# Schema_Proiect_v121.net
KiCad netlist of a schematic drawn in EAGLE
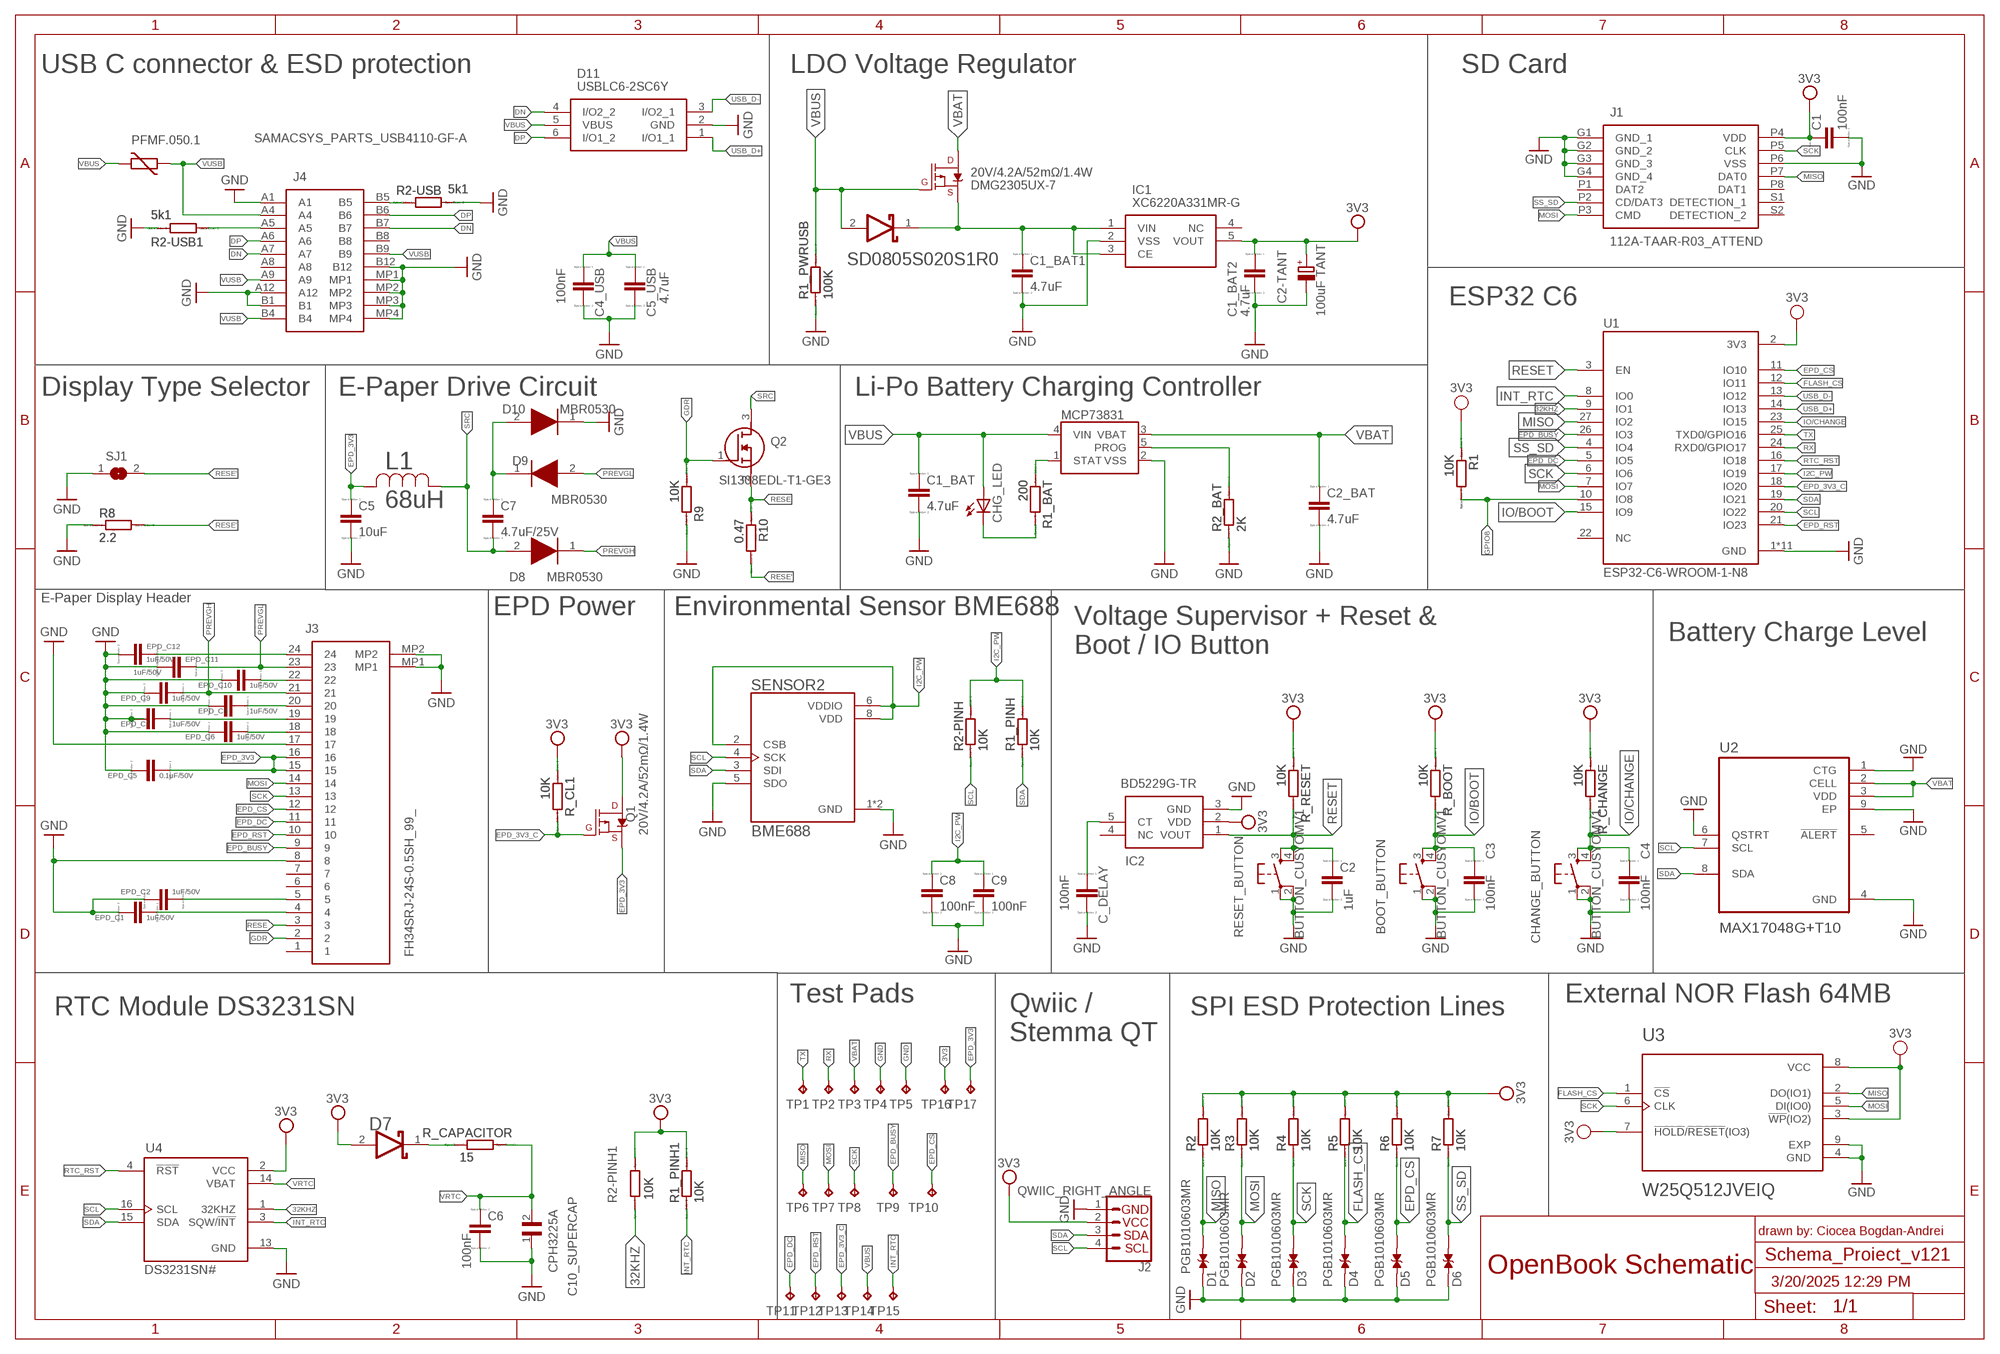
[diagram p0: schematic, sheet 1]

(export (version "E")
  (design (tool "Eeschema 10.0.6"))
  (components
    (comp (ref "BOOT_BUTTON")
      (value "BUTTON_CUSYOMV1")
      (footprint "eagle-import:MYBUTTON")
      (libsource (lib "eagle-import") (part "BUTTON_CUSYOMV1"))
    )
    (comp (ref "C1")
      (value "100nF")
      (footprint "eagle-import:EAGLE-LTSPICE_C0402")
      (libsource (lib "eagle-import") (part "EAGLE-LTSPICE_CC0402"))
    )
    (comp (ref "C1_BAT")
      (value "4.7uF")
      (footprint "eagle-import:EAGLE-LTSPICE_C0402")
      (libsource (lib "eagle-import") (part "EAGLE-LTSPICE_CC0402"))
    )
    (comp (ref "C1_BAT1")
      (value "4.7uF")
      (footprint "eagle-import:EAGLE-LTSPICE_C0402")
      (libsource (lib "eagle-import") (part "EAGLE-LTSPICE_CC0402"))
    )
    (comp (ref "C1_BAT2")
      (value "4.7uF")
      (footprint "eagle-import:EAGLE-LTSPICE_C0402")
      (libsource (lib "eagle-import") (part "EAGLE-LTSPICE_CC0402"))
    )
    (comp (ref "C2")
      (value "1uF")
      (footprint "eagle-import:EAGLE-LTSPICE_C0402")
      (libsource (lib "eagle-import") (part "EAGLE-LTSPICE_CC0402"))
    )
    (comp (ref "C2-TANT")
      (value "100uF TANT")
      (footprint "eagle-import:RCL_CT3528")
      (libsource (lib "eagle-import") (part "RCL_CPOL-EUCT3528"))
    )
    (comp (ref "C2_BAT")
      (value "4.7uF")
      (footprint "eagle-import:EAGLE-LTSPICE_C0402")
      (libsource (lib "eagle-import") (part "EAGLE-LTSPICE_CC0402"))
    )
    (comp (ref "C3")
      (value "100nF")
      (footprint "eagle-import:EAGLE-LTSPICE_C0402")
      (libsource (lib "eagle-import") (part "EAGLE-LTSPICE_CC0402"))
    )
    (comp (ref "C4")
      (value "100nF")
      (footprint "eagle-import:EAGLE-LTSPICE_C0402")
      (libsource (lib "eagle-import") (part "EAGLE-LTSPICE_CC0402"))
    )
    (comp (ref "C4_USB")
      (value "100nF")
      (footprint "eagle-import:EAGLE-LTSPICE_C0402")
      (libsource (lib "eagle-import") (part "EAGLE-LTSPICE_CC0402"))
    )
    (comp (ref "C5")
      (value "10uF")
      (footprint "eagle-import:EAGLE-LTSPICE_C0402")
      (libsource (lib "eagle-import") (part "EAGLE-LTSPICE_CC0402"))
    )
    (comp (ref "C5_USB")
      (value "4.7uF")
      (footprint "eagle-import:EAGLE-LTSPICE_C0402")
      (libsource (lib "eagle-import") (part "EAGLE-LTSPICE_CC0402"))
    )
    (comp (ref "C6")
      (value "100nF")
      (footprint "eagle-import:EAGLE-LTSPICE_C0402")
      (libsource (lib "eagle-import") (part "EAGLE-LTSPICE_CC0402"))
    )
    (comp (ref "C7")
      (value "4.7uF/25V")
      (footprint "eagle-import:EAGLE-LTSPICE_C0402")
      (libsource (lib "eagle-import") (part "EAGLE-LTSPICE_CC0402"))
    )
    (comp (ref "C8")
      (value "100nF")
      (footprint "eagle-import:EAGLE-LTSPICE_C0402")
      (libsource (lib "eagle-import") (part "EAGLE-LTSPICE_CC0402"))
    )
    (comp (ref "C9")
      (value "100nF")
      (footprint "eagle-import:EAGLE-LTSPICE_C0402")
      (libsource (lib "eagle-import") (part "EAGLE-LTSPICE_CC0402"))
    )
    (comp (ref "C10_SUPERCAP")
      (value "CPH3225A")
      (footprint "eagle-import:CAPCP3225X100N")
      (fields (field (name "MF") "Seiko Instruments"))
      (libsource (lib "eagle-import") (part "CPH3225A"))
    )
    (comp (ref "CHANGE_BUTTON")
      (value "BUTTON_CUSYOMV1")
      (footprint "eagle-import:MYBUTTON")
      (libsource (lib "eagle-import") (part "BUTTON_CUSYOMV1"))
    )
    (comp (ref "CHG_LED")
      (value "ADAFRUIT_LEDCHIP-LED0603")
      (footprint "eagle-import:ADAFRUIT_CHIP-LED0603")
      (libsource (lib "eagle-import") (part "ADAFRUIT_LEDCHIP-LED0603"))
    )
    (comp (ref "C_DELAY")
      (value "100nF")
      (footprint "eagle-import:EAGLE-LTSPICE_C0402")
      (libsource (lib "eagle-import") (part "EAGLE-LTSPICE_CC0402"))
    )
    (comp (ref "D1")
      (value "PGB1010603MR")
      (footprint "eagle-import:DIOC1608X36N")
      (fields (field (name "MF") "Littelfuse Inc."))
      (libsource (lib "eagle-import") (part "PGB1010603MR"))
    )
    (comp (ref "D2")
      (value "PGB1010603MR")
      (footprint "eagle-import:DIOC1608X36N")
      (fields (field (name "MF") "Littelfuse Inc."))
      (libsource (lib "eagle-import") (part "PGB1010603MR"))
    )
    (comp (ref "D3")
      (value "PGB1010603MR")
      (footprint "eagle-import:DIOC1608X36N")
      (fields (field (name "MF") "Littelfuse Inc."))
      (libsource (lib "eagle-import") (part "PGB1010603MR"))
    )
    (comp (ref "D4")
      (value "PGB1010603MR")
      (footprint "eagle-import:DIOC1608X36N")
      (fields (field (name "MF") "Littelfuse Inc."))
      (libsource (lib "eagle-import") (part "PGB1010603MR"))
    )
    (comp (ref "D5")
      (value "PGB1010603MR")
      (footprint "eagle-import:DIOC1608X36N")
      (fields (field (name "MF") "Littelfuse Inc."))
      (libsource (lib "eagle-import") (part "PGB1010603MR"))
    )
    (comp (ref "D6")
      (value "PGB1010603MR")
      (footprint "eagle-import:DIOC1608X36N")
      (fields (field (name "MF") "Littelfuse Inc."))
      (libsource (lib "eagle-import") (part "PGB1010603MR"))
    )
    (comp (ref "D7")
      (value "SD0805S020S1R0")
      (footprint "eagle-import:ESP32_WROVER_AVX---SD0805S020S1R0_AVX_SD0805S020S1R0_0")
      (fields
        (field (name "DIGIKEY_PART_NUMBER") "478-7800-1-ND")
        (field (name "MF") "AVX")
        (field (name "MOUSER_PART_NUMBER") "581-SD0805S020S1R0")
      )
      (libsource (lib "eagle-import") (part "ESP32_WROVER_AVX---SD0805S020S1R0_AVX_SD0805S020S1R0_0_0AVX_SD0805S020S1R0_0_0"))
    )
    (comp (ref "D8")
      (value "MBR0530")
      (footprint "eagle-import:SOD3716X135N")
      (fields (field (name "MF") "ON Semiconductor"))
      (libsource (lib "eagle-import") (part "MBR0530"))
    )
    (comp (ref "D9")
      (value "MBR0530")
      (footprint "eagle-import:SOD3716X135N")
      (fields (field (name "MF") "ON Semiconductor"))
      (libsource (lib "eagle-import") (part "MBR0530"))
    )
    (comp (ref "D10")
      (value "MBR0530")
      (footprint "eagle-import:SOD3716X135N")
      (fields (field (name "MF") "ON Semiconductor"))
      (libsource (lib "eagle-import") (part "MBR0530"))
    )
    (comp (ref "D11")
      (value "USBLC6-2SC6Y")
      (footprint "eagle-import:SOT95P280X145-6N")
      (fields (field (name "MF") "STMicroelectronics"))
      (libsource (lib "eagle-import") (part "USBLC6-2SC6Y"))
    )
    (comp (ref "DMG2305UX-7")
      (value "20V/4.2A/52mΩ/1.4W")
      (footprint "eagle-import:ESP32_WROVER_SPARKFUN-DISCRETESEMI_SOT23-3")
      (libsource (lib "eagle-import") (part "ESP32_WROVER_SPARKFUN-DISCRETESEMI_MOSFET_PCH-DMG2305UX-7"))
    )
    (comp (ref "EPD_C1")
      (value "1uF/50V")
      (footprint "eagle-import:EAGLE-LTSPICE_C0402")
      (libsource (lib "eagle-import") (part "EAGLE-LTSPICE_CC0402"))
    )
    (comp (ref "EPD_C2")
      (value "1uF/50V")
      (footprint "eagle-import:EAGLE-LTSPICE_C0402")
      (libsource (lib "eagle-import") (part "EAGLE-LTSPICE_CC0402"))
    )
    (comp (ref "EPD_C5")
      (value "0.1uF/50V")
      (footprint "eagle-import:EAGLE-LTSPICE_C0402")
      (libsource (lib "eagle-import") (part "EAGLE-LTSPICE_CC0402"))
    )
    (comp (ref "EPD_C6")
      (value "1uF/50V")
      (footprint "eagle-import:EAGLE-LTSPICE_C0402")
      (libsource (lib "eagle-import") (part "EAGLE-LTSPICE_CC0402"))
    )
    (comp (ref "EPD_C7")
      (value "1uF/50V")
      (footprint "eagle-import:EAGLE-LTSPICE_C0402")
      (libsource (lib "eagle-import") (part "EAGLE-LTSPICE_CC0402"))
    )
    (comp (ref "EPD_C8")
      (value "1uF/50V")
      (footprint "eagle-import:EAGLE-LTSPICE_C0402")
      (libsource (lib "eagle-import") (part "EAGLE-LTSPICE_CC0402"))
    )
    (comp (ref "EPD_C9")
      (value "1uF/50V")
      (footprint "eagle-import:EAGLE-LTSPICE_C0402")
      (libsource (lib "eagle-import") (part "EAGLE-LTSPICE_CC0402"))
    )
    (comp (ref "EPD_C10")
      (value "1uF/50V")
      (footprint "eagle-import:EAGLE-LTSPICE_C0402")
      (libsource (lib "eagle-import") (part "EAGLE-LTSPICE_CC0402"))
    )
    (comp (ref "EPD_C11")
      (value "1uF/50V")
      (footprint "eagle-import:EAGLE-LTSPICE_C0402")
      (libsource (lib "eagle-import") (part "EAGLE-LTSPICE_CC0402"))
    )
    (comp (ref "EPD_C12")
      (value "1uF/50V")
      (footprint "eagle-import:EAGLE-LTSPICE_C0402")
      (libsource (lib "eagle-import") (part "EAGLE-LTSPICE_CC0402"))
    )
    (comp (ref "IC1")
      (value "XC6220A331MR-G")
      (footprint "eagle-import:SOT95P280X120-5N")
      (fields (field (name "MOUSER_PART_NUMBER") "865-XC6220A331MR-G"))
      (libsource (lib "eagle-import") (part "XC6220A331MR-G"))
    )
    (comp (ref "IC2")
      (value "BD5229G-TR")
      (footprint "eagle-import:SOT95P280X125-5N")
      (fields (field (name "MOUSER_PART_NUMBER") "755-BD5229G-TR"))
      (libsource (lib "eagle-import") (part "BD5229G-TR"))
    )
    (comp (ref "J1")
      (value "112A-TAAR-R03_ATTEND")
      (footprint "eagle-import:112ATAARR03ATTEND")
      (fields (field (name "MANUFACTURER_PART_NUMBER") "112A-TAAR-R03 ATTEND"))
      (libsource (lib "eagle-import") (part "112A-TAAR-R03_ATTEND"))
    )
    (comp (ref "J2")
      (value "QWIIC_RIGHT_ANGLE")
      (footprint "eagle-import:JST04_1MM_RA")
      (libsource (lib "eagle-import") (part "QWIIC_CONNECTORJS-1MM"))
    )
    (comp (ref "J3")
      (value "FH34SRJ-24S-0.5SH_99_")
      (footprint "eagle-import:FH34SRJ24S05SH99")
      (fields
        (field (name "MANUFACTURER_PART_NUMBER") "FH34SRJ-24S-0.5SH(99)")
        (field (name "MOUSER_PART_NUMBER") "798-FH34SRJ24S05SH99")
      )
      (libsource (lib "eagle-import") (part "FH34SRJ-24S-0.5SH_99_"))
    )
    (comp (ref "J4")
      (value "SAMACSYS_PARTS_USB4110-GF-A")
      (footprint "eagle-import:SAMACSYS_PARTS_USB4110GFA")
      (fields
        (field (name "MANUFACTURER_PART_NUMBER") "USB4110-GF-A")
        (field (name "MOUSER_PART_NUMBER") "640-USB4110-GF-A")
      )
      (libsource (lib "eagle-import") (part "SAMACSYS_PARTS_USB4110-GF-A"))
    )
    (comp (ref "L1")
      (value "68uH")
      (footprint "eagle-import:IND_4828-WE-TPC_WRE")
      (fields
        (field (name "MANUFACTURER_PART_NUMBER") "744043680")
        (field (name "COPYRIGHT") "Copyright (C) 2024 Ultra Librarian. All rights reserved.")
      )
      (libsource (lib "eagle-import") (part "744043680IND_4828-WE-TPC_WRE"))
    )
    (comp (ref "MCP73831")
      (value "ESP32_WROVER_SPARKFUN-IC-POWER_MCP73831")
      (footprint "eagle-import:ESP32_WROVER_SPARKFUN-IC-POWER_SOT23-5")
      (libsource (lib "eagle-import") (part "ESP32_WROVER_SPARKFUN-IC-POWER_MCP73831"))
    )
    (comp (ref "PFMF.050.1")
      (value "ESP32C6_VARISTORCN1812")
      (footprint "eagle-import:ESP32C6_VARISTOR_CT_CN1812")
      (libsource (lib "eagle-import") (part "ESP32C6_VARISTORCN1812"))
    )
    (comp (ref "Q1")
      (value "20V/4.2A/52mΩ/1.4W")
      (footprint "eagle-import:ESP32_WROVER_SPARKFUN-DISCRETESEMI_SOT23-3")
      (libsource (lib "eagle-import") (part "ESP32_WROVER_SPARKFUN-DISCRETESEMI_MOSFET_PCH-DMG2305UX-7"))
    )
    (comp (ref "Q2")
      (value "SI1308EDL-T1-GE3")
      (footprint "eagle-import:SOT65P210X110-3N")
      (fields (field (name "MF") "Vishay Siliconix"))
      (libsource (lib "eagle-import") (part "SI1308EDL-T1-GE3"))
    )
    (comp (ref "R1")
      (value "10K")
      (footprint "eagle-import:ESP32_WROVER_EAGLE-LTSPICE_R0402")
      (libsource (lib "eagle-import") (part "ESP32_WROVER_EAGLE-LTSPICE_RR0402"))
    )
    (comp (ref "R1_BAT")
      (value "200")
      (footprint "eagle-import:ESP32_WROVER_EAGLE-LTSPICE_R0402")
      (libsource (lib "eagle-import") (part "ESP32_WROVER_EAGLE-LTSPICE_RR0402"))
    )
    (comp (ref "R1_PINH")
      (value "10K")
      (footprint "eagle-import:ESP32_WROVER_EAGLE-LTSPICE_R0402")
      (libsource (lib "eagle-import") (part "ESP32_WROVER_EAGLE-LTSPICE_RR0402"))
    )
    (comp (ref "R1_PINH1")
      (value "10K")
      (footprint "eagle-import:ESP32_WROVER_EAGLE-LTSPICE_R0402")
      (libsource (lib "eagle-import") (part "ESP32_WROVER_EAGLE-LTSPICE_RR0402"))
    )
    (comp (ref "R1_PWRUSB")
      (value "100K")
      (footprint "eagle-import:ESP32_WROVER_EAGLE-LTSPICE_R0402")
      (libsource (lib "eagle-import") (part "ESP32_WROVER_EAGLE-LTSPICE_RR0402"))
    )
    (comp (ref "R2")
      (value "10K")
      (footprint "eagle-import:ESP32_WROVER_EAGLE-LTSPICE_R0402")
      (libsource (lib "eagle-import") (part "ESP32_WROVER_EAGLE-LTSPICE_RR0402"))
    )
    (comp (ref "R2-PINH")
      (value "10K")
      (footprint "eagle-import:ESP32_WROVER_EAGLE-LTSPICE_R0402")
      (libsource (lib "eagle-import") (part "ESP32_WROVER_EAGLE-LTSPICE_RR0402"))
    )
    (comp (ref "R2-PINH1")
      (value "10K")
      (footprint "eagle-import:ESP32_WROVER_EAGLE-LTSPICE_R0402")
      (libsource (lib "eagle-import") (part "ESP32_WROVER_EAGLE-LTSPICE_RR0402"))
    )
    (comp (ref "R2-USB")
      (value "5k1")
      (footprint "eagle-import:ESP32_WROVER_EAGLE-LTSPICE_R0402")
      (libsource (lib "eagle-import") (part "ESP32_WROVER_EAGLE-LTSPICE_RR0402"))
    )
    (comp (ref "R2-USB1")
      (value "5k1")
      (footprint "eagle-import:ESP32_WROVER_EAGLE-LTSPICE_R0402")
      (libsource (lib "eagle-import") (part "ESP32_WROVER_EAGLE-LTSPICE_RR0402"))
    )
    (comp (ref "R2_BAT")
      (value "2K")
      (footprint "eagle-import:ESP32_WROVER_EAGLE-LTSPICE_R0402")
      (libsource (lib "eagle-import") (part "ESP32_WROVER_EAGLE-LTSPICE_RR0402"))
    )
    (comp (ref "R3")
      (value "10K")
      (footprint "eagle-import:ESP32_WROVER_EAGLE-LTSPICE_R0402")
      (libsource (lib "eagle-import") (part "ESP32_WROVER_EAGLE-LTSPICE_RR0402"))
    )
    (comp (ref "R4")
      (value "10K")
      (footprint "eagle-import:ESP32_WROVER_EAGLE-LTSPICE_R0402")
      (libsource (lib "eagle-import") (part "ESP32_WROVER_EAGLE-LTSPICE_RR0402"))
    )
    (comp (ref "R5")
      (value "10K")
      (footprint "eagle-import:ESP32_WROVER_EAGLE-LTSPICE_R0402")
      (libsource (lib "eagle-import") (part "ESP32_WROVER_EAGLE-LTSPICE_RR0402"))
    )
    (comp (ref "R6")
      (value "10K")
      (footprint "eagle-import:ESP32_WROVER_EAGLE-LTSPICE_R0402")
      (libsource (lib "eagle-import") (part "ESP32_WROVER_EAGLE-LTSPICE_RR0402"))
    )
    (comp (ref "R7")
      (value "10K")
      (footprint "eagle-import:ESP32_WROVER_EAGLE-LTSPICE_R0402")
      (libsource (lib "eagle-import") (part "ESP32_WROVER_EAGLE-LTSPICE_RR0402"))
    )
    (comp (ref "R8")
      (value "2.2")
      (footprint "eagle-import:ESP32_WROVER_EAGLE-LTSPICE_R0402")
      (libsource (lib "eagle-import") (part "ESP32_WROVER_EAGLE-LTSPICE_RR0402"))
    )
    (comp (ref "R9")
      (value "10K")
      (footprint "eagle-import:ESP32_WROVER_EAGLE-LTSPICE_R0402")
      (libsource (lib "eagle-import") (part "ESP32_WROVER_EAGLE-LTSPICE_RR0402"))
    )
    (comp (ref "R10")
      (value "0.47")
      (footprint "eagle-import:ESP32_WROVER_EAGLE-LTSPICE_R0402")
      (libsource (lib "eagle-import") (part "ESP32_WROVER_EAGLE-LTSPICE_RR0402"))
    )
    (comp (ref "RESET_BUTTON")
      (value "BUTTON_CUSYOMV1")
      (footprint "eagle-import:MYBUTTON")
      (libsource (lib "eagle-import") (part "BUTTON_CUSYOMV1"))
    )
    (comp (ref "R_BOOT")
      (value "10K")
      (footprint "eagle-import:ESP32_WROVER_EAGLE-LTSPICE_R0402")
      (libsource (lib "eagle-import") (part "ESP32_WROVER_EAGLE-LTSPICE_RR0402"))
    )
    (comp (ref "R_CAPACITOR")
      (value "15")
      (footprint "eagle-import:ESP32_WROVER_EAGLE-LTSPICE_R0402")
      (libsource (lib "eagle-import") (part "ESP32_WROVER_EAGLE-LTSPICE_RR0402"))
    )
    (comp (ref "R_CHANGE")
      (value "10K")
      (footprint "eagle-import:ESP32_WROVER_EAGLE-LTSPICE_R0402")
      (libsource (lib "eagle-import") (part "ESP32_WROVER_EAGLE-LTSPICE_RR0402"))
    )
    (comp (ref "R_CL1")
      (value "10K")
      (footprint "eagle-import:ESP32_WROVER_EAGLE-LTSPICE_R0402")
      (libsource (lib "eagle-import") (part "ESP32_WROVER_EAGLE-LTSPICE_RR0402"))
    )
    (comp (ref "R_RESET")
      (value "10K")
      (footprint "eagle-import:ESP32_WROVER_EAGLE-LTSPICE_R0402")
      (libsource (lib "eagle-import") (part "ESP32_WROVER_EAGLE-LTSPICE_RR0402"))
    )
    (comp (ref "SD0805S020S1R0")
      (value "ESP32_WROVER_AVX---SD0805S020S1R0_AVX_SD0805S020S1R0_0_0AVX_SD0805S020S1R0_0_0")
      (footprint "eagle-import:ESP32_WROVER_AVX---SD0805S020S1R0_AVX_SD0805S020S1R0_0")
      (fields
        (field (name "DIGIKEY_PART_NUMBER") "478-7800-1-ND")
        (field (name "MF") "AVX")
        (field (name "MOUSER_PART_NUMBER") "581-SD0805S020S1R0")
      )
      (libsource (lib "eagle-import") (part "ESP32_WROVER_AVX---SD0805S020S1R0_AVX_SD0805S020S1R0_0_0AVX_SD0805S020S1R0_0_0"))
    )
    (comp (ref "SENSOR2")
      (value "BME688")
      (footprint "eagle-import:ESP32_WROVER_BME680_PSON80P300X300X100-8N")
      (fields (field (name "MF") "Bosch Sensortec") (field (name "MP") "BME680"))
      (libsource (lib "eagle-import") (part "ESP32_WROVER_BME680_BME680"))
    )
    (comp (ref "SJ1") (value "SJ") (footprint "eagle-import:SJ") (libsource (lib "eagle-import") (part "SJ")))
    (comp (ref "TP1")
      (value "TX")
      (footprint "eagle-import:TP20R")
      (libsource (lib "eagle-import") (part "TPTP20R"))
    )
    (comp (ref "TP2")
      (value "RX")
      (footprint "eagle-import:TP20R")
      (libsource (lib "eagle-import") (part "TPTP20R"))
    )
    (comp (ref "TP3")
      (value "VBAT")
      (footprint "eagle-import:TP20R")
      (libsource (lib "eagle-import") (part "TPTP20R"))
    )
    (comp (ref "TP4")
      (value "GND")
      (footprint "eagle-import:TP20R")
      (libsource (lib "eagle-import") (part "TPTP20R"))
    )
    (comp (ref "TP5")
      (value "GND")
      (footprint "eagle-import:TP20R")
      (libsource (lib "eagle-import") (part "TPTP20R"))
    )
    (comp (ref "TP6")
      (value "MISO")
      (footprint "eagle-import:TP20R")
      (libsource (lib "eagle-import") (part "TPTP20R"))
    )
    (comp (ref "TP7")
      (value "MOSI")
      (footprint "eagle-import:TP20R")
      (libsource (lib "eagle-import") (part "TPTP20R"))
    )
    (comp (ref "TP8")
      (value "SCK")
      (footprint "eagle-import:TP20R")
      (libsource (lib "eagle-import") (part "TPTP20R"))
    )
    (comp (ref "TP9")
      (value "EPD_BUSY")
      (footprint "eagle-import:TP20R")
      (libsource (lib "eagle-import") (part "TPTP20R"))
    )
    (comp (ref "TP10")
      (value "EPD_CS")
      (footprint "eagle-import:TP20R")
      (libsource (lib "eagle-import") (part "TPTP20R"))
    )
    (comp (ref "TP11")
      (value "EPD_DC")
      (footprint "eagle-import:TP20R")
      (libsource (lib "eagle-import") (part "TPTP20R"))
    )
    (comp (ref "TP12")
      (value "EPD_RST")
      (footprint "eagle-import:TP20R")
      (libsource (lib "eagle-import") (part "TPTP20R"))
    )
    (comp (ref "TP13")
      (value "EPD_3V3_C")
      (footprint "eagle-import:TP20R")
      (libsource (lib "eagle-import") (part "TPTP20R"))
    )
    (comp (ref "TP14")
      (value "VBUS")
      (footprint "eagle-import:TP20R")
      (libsource (lib "eagle-import") (part "TPTP20R"))
    )
    (comp (ref "TP15")
      (value "INT_RTC")
      (footprint "eagle-import:TP20R")
      (libsource (lib "eagle-import") (part "TPTP20R"))
    )
    (comp (ref "TP16")
      (value "3V3")
      (footprint "eagle-import:TP20R")
      (libsource (lib "eagle-import") (part "TPTP20R"))
    )
    (comp (ref "TP17")
      (value "EPD_3V3")
      (footprint "eagle-import:TP20R")
      (libsource (lib "eagle-import") (part "TPTP20R"))
    )
    (comp (ref "U1")
      (value "ESP32-C6-WROOM-1-N8")
      (footprint "eagle-import:XCVR_ESP32-C6-WROOM-1-N8")
      (fields (field (name "MF") "Espressif Systems"))
      (libsource (lib "eagle-import") (part "ESP32-C6-WROOM-1-N8"))
    )
    (comp (ref "U2")
      (value "MAX17048G+T10")
      (footprint "eagle-import:SON50P200X200X80-9N")
      (fields (field (name "MF") "Analog Devices"))
      (libsource (lib "eagle-import") (part "MAX17048G+T10"))
    )
    (comp (ref "U3")
      (value "W25Q512JVEIQ")
      (footprint "eagle-import:SON127P600X800X80-9N")
      (fields (field (name "MF") "Winbond Electronics"))
      (libsource (lib "eagle-import") (part "W25Q512JVEIQ"))
    )
    (comp (ref "U4")
      (value "DS3231SN#")
      (footprint "eagle-import:SOIC127P1032X265-16N")
      (fields (field (name "MF") "Analog Devices"))
      (libsource (lib "eagle-import") (part "DS3231SN#"))
    )
  )
  (nets
    (net (code "1") (name "3V3") (class "Default")
      (node (ref "C1") (pin "1") (pinfunction "1_1") (pintype "passive"))
      (node (ref "C1_BAT2") (pin "1") (pinfunction "1_1") (pintype "passive"))
      (node (ref "C2-TANT") (pin "+") (pinfunction "+_+") (pintype "passive"))
      (node (ref "D7") (pin "2") (pinfunction "ANODE_2") (pintype "bidirectional"))
      (node (ref "IC1") (pin "5") (pinfunction "VOUT_5") (pintype "bidirectional"))
      (node (ref "IC2") (pin "2") (pinfunction "VDD_2") (pintype "bidirectional"))
      (node (ref "J1") (pin "P4") (pinfunction "VDD_P4") (pintype "bidirectional"))
      (node (ref "J2") (pin "2") (pinfunction "2_2") (pintype "power_in"))
      (node (ref "Q1") (pin "3") (pinfunction "D_3") (pintype "bidirectional"))
      (node (ref "R1") (pin "1") (pinfunction "1_1") (pintype "passive"))
      (node (ref "R1_PINH1") (pin "2") (pinfunction "2_2") (pintype "passive"))
      (node (ref "R2") (pin "2") (pinfunction "2_2") (pintype "passive"))
      (node (ref "R2-PINH1") (pin "1") (pinfunction "1_1") (pintype "passive"))
      (node (ref "R3") (pin "2") (pinfunction "2_2") (pintype "passive"))
      (node (ref "R4") (pin "2") (pinfunction "2_2") (pintype "passive"))
      (node (ref "R5") (pin "2") (pinfunction "2_2") (pintype "passive"))
      (node (ref "R6") (pin "2") (pinfunction "2_2") (pintype "passive"))
      (node (ref "R7") (pin "2") (pinfunction "2_2") (pintype "passive"))
      (node (ref "R_BOOT") (pin "1") (pinfunction "1_1") (pintype "passive"))
      (node (ref "R_CHANGE") (pin "1") (pinfunction "1_1") (pintype "passive"))
      (node (ref "R_CL1") (pin "1") (pinfunction "1_1") (pintype "passive"))
      (node (ref "R_RESET") (pin "1") (pinfunction "1_1") (pintype "passive"))
      (node (ref "TP16") (pin "TP") (pinfunction "TP_TP") (pintype "input"))
      (node (ref "U1") (pin "2") (pinfunction "3V3_2") (pintype "power_in"))
      (node (ref "U3") (pin "3") (pinfunction "~{WP}(IO2)_3") (pintype "bidirectional"))
      (node (ref "U3") (pin "7") (pinfunction "~{HOLD}/~{RESET}(IO3)_7") (pintype "bidirectional"))
      (node (ref "U3") (pin "8") (pinfunction "VCC_8") (pintype "power_in"))
      (node (ref "U4") (pin "2") (pinfunction "VCC_2") (pintype "power_in"))
    )
    (net (code "2") (name "32KHZ") (class "Default")
      (node (ref "R2-PINH1") (pin "2") (pinfunction "2_2") (pintype "passive"))
      (node (ref "U1") (pin "9") (pinfunction "IO1_9") (pintype "bidirectional"))
      (node (ref "U4") (pin "1") (pinfunction "32KHZ_1") (pintype "output"))
    )
    (net (code "3") (name "DN") (class "Default")
      (node (ref "D11") (pin "4") (pinfunction "I/O2_2_4") (pintype "bidirectional"))
      (node (ref "J4") (pin "A7") (pinfunction "A7_A7") (pintype "bidirectional"))
      (node (ref "J4") (pin "B7") (pinfunction "B7_B7") (pintype "bidirectional"))
    )
    (net (code "4") (name "DP") (class "Default")
      (node (ref "D11") (pin "6") (pinfunction "I/O1_2_6") (pintype "bidirectional"))
      (node (ref "J4") (pin "A6") (pinfunction "A6_A6") (pintype "bidirectional"))
      (node (ref "J4") (pin "B6") (pinfunction "B6_B6") (pintype "bidirectional"))
    )
    (net (code "5") (name "EPD_3V3") (class "Default")
      (node (ref "C5") (pin "1") (pinfunction "1_1") (pintype "passive"))
      (node (ref "EPD_C5") (pin "1") (pinfunction "1_1") (pintype "passive"))
      (node (ref "J3") (pin "15") (pinfunction "15_15") (pintype "bidirectional"))
      (node (ref "J3") (pin "16") (pinfunction "16_16") (pintype "bidirectional"))
      (node (ref "L1") (pin "2") (pinfunction "2_2") (pintype "passive"))
      (node (ref "Q1") (pin "2") (pinfunction "S_2") (pintype "bidirectional"))
      (node (ref "TP17") (pin "TP") (pinfunction "TP_TP") (pintype "input"))
    )
    (net (code "6") (name "EPD_3V3_C") (class "Default")
      (node (ref "Q1") (pin "1") (pinfunction "G_1") (pintype "bidirectional"))
      (node (ref "R_CL1") (pin "2") (pinfunction "2_2") (pintype "passive"))
      (node (ref "TP13") (pin "TP") (pinfunction "TP_TP") (pintype "input"))
      (node (ref "U1") (pin "18") (pinfunction "IO20_18") (pintype "bidirectional"))
    )
    (net (code "7") (name "EPD_BUSY") (class "Default")
      (node (ref "J3") (pin "9") (pinfunction "9_9") (pintype "bidirectional"))
      (node (ref "TP9") (pin "TP") (pinfunction "TP_TP") (pintype "input"))
      (node (ref "U1") (pin "26") (pinfunction "IO3_26") (pintype "bidirectional"))
    )
    (net (code "8") (name "EPD_CS") (class "Default")
      (node (ref "D5") (pin "2") (pinfunction "2_2") (pintype "passive"))
      (node (ref "J3") (pin "12") (pinfunction "12_12") (pintype "bidirectional"))
      (node (ref "R6") (pin "1") (pinfunction "1_1") (pintype "passive"))
      (node (ref "TP10") (pin "TP") (pinfunction "TP_TP") (pintype "input"))
      (node (ref "U1") (pin "11") (pinfunction "IO10_11") (pintype "bidirectional"))
    )
    (net (code "9") (name "EPD_DC") (class "Default")
      (node (ref "J3") (pin "11") (pinfunction "11_11") (pintype "bidirectional"))
      (node (ref "TP11") (pin "TP") (pinfunction "TP_TP") (pintype "input"))
      (node (ref "U1") (pin "5") (pinfunction "IO5_5") (pintype "bidirectional"))
    )
    (net (code "10") (name "EPD_RST") (class "Default")
      (node (ref "J3") (pin "10") (pinfunction "10_10") (pintype "bidirectional"))
      (node (ref "TP12") (pin "TP") (pinfunction "TP_TP") (pintype "input"))
      (node (ref "U1") (pin "21") (pinfunction "IO23_21") (pintype "bidirectional"))
    )
    (net (code "11") (name "FLASH_CS") (class "Default")
      (node (ref "D4") (pin "2") (pinfunction "2_2") (pintype "passive"))
      (node (ref "R5") (pin "1") (pinfunction "1_1") (pintype "passive"))
      (node (ref "U1") (pin "12") (pinfunction "IO11_12") (pintype "bidirectional"))
      (node (ref "U3") (pin "1") (pinfunction "~{CS}_1") (pintype "input"))
    )
    (net (code "12") (name "GDR") (class "Default")
      (node (ref "J3") (pin "2") (pinfunction "2_2") (pintype "bidirectional"))
      (node (ref "Q2") (pin "1") (pinfunction "G_1") (pintype "bidirectional"))
      (node (ref "R9") (pin "1") (pinfunction "1_1") (pintype "passive"))
    )
    (net (code "13") (name "GND") (class "Default")
      (node (ref "BOOT_BUTTON") (pin "1") (pinfunction "1_1") (pintype "passive"))
      (node (ref "BOOT_BUTTON") (pin "2") (pinfunction "2_2") (pintype "passive"))
      (node (ref "C1") (pin "2") (pinfunction "2_2") (pintype "passive"))
      (node (ref "C10_SUPERCAP") (pin "1") (pinfunction "1_1") (pintype "passive"))
      (node (ref "C1_BAT") (pin "2") (pinfunction "2_2") (pintype "passive"))
      (node (ref "C1_BAT1") (pin "2") (pinfunction "2_2") (pintype "passive"))
      (node (ref "C1_BAT2") (pin "2") (pinfunction "2_2") (pintype "passive"))
      (node (ref "C2") (pin "2") (pinfunction "2_2") (pintype "passive"))
      (node (ref "C2-TANT") (pin "-") (pinfunction "-_-") (pintype "passive"))
      (node (ref "C2_BAT") (pin "2") (pinfunction "2_2") (pintype "passive"))
      (node (ref "C3") (pin "2") (pinfunction "2_2") (pintype "passive"))
      (node (ref "C4") (pin "2") (pinfunction "2_2") (pintype "passive"))
      (node (ref "C4_USB") (pin "2") (pinfunction "2_2") (pintype "passive"))
      (node (ref "C5") (pin "2") (pinfunction "2_2") (pintype "passive"))
      (node (ref "C5_USB") (pin "2") (pinfunction "2_2") (pintype "passive"))
      (node (ref "C6") (pin "2") (pinfunction "2_2") (pintype "passive"))
      (node (ref "C8") (pin "2") (pinfunction "2_2") (pintype "passive"))
      (node (ref "C9") (pin "2") (pinfunction "2_2") (pintype "passive"))
      (node (ref "CHANGE_BUTTON") (pin "1") (pinfunction "1_1") (pintype "passive"))
      (node (ref "CHANGE_BUTTON") (pin "2") (pinfunction "2_2") (pintype "passive"))
      (node (ref "C_DELAY") (pin "2") (pinfunction "2_2") (pintype "passive"))
      (node (ref "D1") (pin "1") (pinfunction "1_1") (pintype "passive"))
      (node (ref "D10") (pin "1") (pinfunction "K_1") (pintype "bidirectional"))
      (node (ref "D11") (pin "2") (pinfunction "GND_2") (pintype "bidirectional"))
      (node (ref "D2") (pin "1") (pinfunction "1_1") (pintype "passive"))
      (node (ref "D3") (pin "1") (pinfunction "1_1") (pintype "passive"))
      (node (ref "D4") (pin "1") (pinfunction "1_1") (pintype "passive"))
      (node (ref "D5") (pin "1") (pinfunction "1_1") (pintype "passive"))
      (node (ref "D6") (pin "1") (pinfunction "1_1") (pintype "passive"))
      (node (ref "EPD_C1") (pin "2") (pinfunction "2_2") (pintype "passive"))
      (node (ref "EPD_C10") (pin "2") (pinfunction "2_2") (pintype "passive"))
      (node (ref "EPD_C11") (pin "2") (pinfunction "2_2") (pintype "passive"))
      (node (ref "EPD_C12") (pin "2") (pinfunction "2_2") (pintype "passive"))
      (node (ref "EPD_C2") (pin "2") (pinfunction "2_2") (pintype "passive"))
      (node (ref "EPD_C5") (pin "2") (pinfunction "2_2") (pintype "passive"))
      (node (ref "EPD_C6") (pin "2") (pinfunction "2_2") (pintype "passive"))
      (node (ref "EPD_C7") (pin "2") (pinfunction "2_2") (pintype "passive"))
      (node (ref "EPD_C8") (pin "2") (pinfunction "2_2") (pintype "passive"))
      (node (ref "EPD_C9") (pin "2") (pinfunction "2_2") (pintype "passive"))
      (node (ref "IC1") (pin "2") (pinfunction "VSS_2") (pintype "bidirectional"))
      (node (ref "IC2") (pin "3") (pinfunction "GND_3") (pintype "bidirectional"))
      (node (ref "J1") (pin "G1") (pinfunction "GND_1_G1") (pintype "bidirectional"))
      (node (ref "J1") (pin "G2") (pinfunction "GND_2_G2") (pintype "bidirectional"))
      (node (ref "J1") (pin "G3") (pinfunction "GND_3_G3") (pintype "bidirectional"))
      (node (ref "J1") (pin "G4") (pinfunction "GND_4_G4") (pintype "bidirectional"))
      (node (ref "J1") (pin "P6") (pinfunction "VSS_P6") (pintype "bidirectional"))
      (node (ref "J2") (pin "1") (pinfunction "1_1") (pintype "power_in"))
      (node (ref "J3") (pin "17") (pinfunction "17_17") (pintype "bidirectional"))
      (node (ref "J3") (pin "8") (pinfunction "8_8") (pintype "bidirectional"))
      (node (ref "J3") (pin "MP1") (pinfunction "MP1_MP1") (pintype "bidirectional"))
      (node (ref "J3") (pin "MP2") (pinfunction "MP2_MP2") (pintype "bidirectional"))
      (node (ref "J4") (pin "A1") (pinfunction "A1_A1") (pintype "bidirectional"))
      (node (ref "J4") (pin "A12") (pinfunction "A12_A12") (pintype "bidirectional"))
      (node (ref "J4") (pin "B1") (pinfunction "B1_B1") (pintype "bidirectional"))
      (node (ref "J4") (pin "B12") (pinfunction "B12_B12") (pintype "bidirectional"))
      (node (ref "J4") (pin "MP1") (pinfunction "MP1_MP1") (pintype "bidirectional"))
      (node (ref "J4") (pin "MP2") (pinfunction "MP2_MP2") (pintype "bidirectional"))
      (node (ref "J4") (pin "MP3") (pinfunction "MP3_MP3") (pintype "bidirectional"))
      (node (ref "J4") (pin "MP4") (pinfunction "MP4_MP4") (pintype "bidirectional"))
      (node (ref "MCP73831") (pin "2") (pinfunction "VSS_2") (pintype "power_in"))
      (node (ref "R1_PWRUSB") (pin "1") (pinfunction "1_1") (pintype "passive"))
      (node (ref "R2-USB") (pin "2") (pinfunction "2_2") (pintype "passive"))
      (node (ref "R2-USB1") (pin "1") (pinfunction "1_1") (pintype "passive"))
      (node (ref "R2_BAT") (pin "1") (pinfunction "1_1") (pintype "passive"))
      (node (ref "R8") (pin "1") (pinfunction "1_1") (pintype "passive"))
      (node (ref "R9") (pin "2") (pinfunction "2_2") (pintype "passive"))
      (node (ref "RESET_BUTTON") (pin "1") (pinfunction "1_1") (pintype "passive"))
      (node (ref "RESET_BUTTON") (pin "2") (pinfunction "2_2") (pintype "passive"))
      (node (ref "SENSOR2") (pin "1") (pinfunction "GND_1") (pintype "power_in"))
      (node (ref "SENSOR2") (pin "5") (pinfunction "SDO_5") (pintype "bidirectional"))
      (node (ref "SENSOR2") (pin "7") (pinfunction "GND_7") (pintype "power_in"))
      (node (ref "SJ1") (pin "1") (pinfunction "1_1") (pintype "passive"))
      (node (ref "TP4") (pin "TP") (pinfunction "TP_TP") (pintype "input"))
      (node (ref "TP5") (pin "TP") (pinfunction "TP_TP") (pintype "input"))
      (node (ref "U1") (pin "1") (pinfunction "GND_1") (pintype "power_in"))
      (node (ref "U1") (pin "28") (pinfunction "GND_28") (pintype "power_in"))
      (node (ref "U1") (pin "29_1") (pinfunction "GND_29_1") (pintype "power_in"))
      (node (ref "U1") (pin "29_2") (pinfunction "GND_29_2") (pintype "power_in"))
      (node (ref "U1") (pin "29_3") (pinfunction "GND_29_3") (pintype "power_in"))
      (node (ref "U1") (pin "29_4") (pinfunction "GND_29_4") (pintype "power_in"))
      (node (ref "U1") (pin "29_5") (pinfunction "GND_29_5") (pintype "power_in"))
      (node (ref "U1") (pin "29_6") (pinfunction "GND_29_6") (pintype "power_in"))
      (node (ref "U1") (pin "29_7") (pinfunction "GND_29_7") (pintype "power_in"))
      (node (ref "U1") (pin "29_8") (pinfunction "GND_29_8") (pintype "power_in"))
      (node (ref "U1") (pin "29_9") (pinfunction "GND_29_9") (pintype "power_in"))
      (node (ref "U2") (pin "1") (pinfunction "CTG_1") (pintype "power_in"))
      (node (ref "U2") (pin "4") (pinfunction "GND_4") (pintype "power_in"))
      (node (ref "U2") (pin "6") (pinfunction "QSTRT_6") (pintype "input"))
      (node (ref "U2") (pin "9") (pinfunction "EP_9") (pintype "power_in"))
      (node (ref "U3") (pin "4") (pinfunction "GND_4") (pintype "power_in"))
      (node (ref "U3") (pin "9") (pinfunction "EXP_9") (pintype "passive"))
      (node (ref "U4") (pin "13") (pinfunction "GND_13") (pintype "power_in"))
    )
    (net (code "14") (name "GPIO8") (class "Default")
      (node (ref "R1") (pin "2") (pinfunction "2_2") (pintype "passive"))
      (node (ref "U1") (pin "10") (pinfunction "IO8_10") (pintype "bidirectional"))
    )
    (net (code "15") (name "I2C_PW") (class "Default")
      (node (ref "C8") (pin "1") (pinfunction "1_1") (pintype "passive"))
      (node (ref "C9") (pin "1") (pinfunction "1_1") (pintype "passive"))
      (node (ref "R1_PINH") (pin "2") (pinfunction "2_2") (pintype "passive"))
      (node (ref "R2-PINH") (pin "2") (pinfunction "2_2") (pintype "passive"))
      (node (ref "SENSOR2") (pin "2") (pinfunction "CSB_2") (pintype "input"))
      (node (ref "SENSOR2") (pin "6") (pinfunction "VDDIO_6") (pintype "power_in"))
      (node (ref "SENSOR2") (pin "8") (pinfunction "VDD_8") (pintype "power_in"))
      (node (ref "U1") (pin "17") (pinfunction "IO19_17") (pintype "bidirectional"))
    )
    (net (code "16") (name "INT_RTC") (class "Default")
      (node (ref "R1_PINH1") (pin "1") (pinfunction "1_1") (pintype "passive"))
      (node (ref "TP15") (pin "TP") (pinfunction "TP_TP") (pintype "input"))
      (node (ref "U1") (pin "8") (pinfunction "IO0_8") (pintype "bidirectional"))
      (node (ref "U4") (pin "3") (pinfunction "SQW/~{INT}_3") (pintype "output"))
    )
    (net (code "17") (name "IO{slash}BOOT") (class "Default")
      (node (ref "BOOT_BUTTON") (pin "3") (pinfunction "3_3") (pintype "passive"))
      (node (ref "BOOT_BUTTON") (pin "4") (pinfunction "4_4") (pintype "passive"))
      (node (ref "C3") (pin "1") (pinfunction "1_1") (pintype "passive"))
      (node (ref "R_BOOT") (pin "2") (pinfunction "2_2") (pintype "passive"))
      (node (ref "U1") (pin "15") (pinfunction "IO9_15") (pintype "bidirectional"))
    )
    (net (code "18") (name "IO{slash}CHANGE") (class "Default")
      (node (ref "C4") (pin "1") (pinfunction "1_1") (pintype "passive"))
      (node (ref "CHANGE_BUTTON") (pin "3") (pinfunction "3_3") (pintype "passive"))
      (node (ref "CHANGE_BUTTON") (pin "4") (pinfunction "4_4") (pintype "passive"))
      (node (ref "R_CHANGE") (pin "2") (pinfunction "2_2") (pintype "passive"))
      (node (ref "U1") (pin "23") (pinfunction "IO15_23") (pintype "bidirectional"))
    )
    (net (code "19") (name "MISO") (class "Default")
      (node (ref "D1") (pin "2") (pinfunction "2_2") (pintype "passive"))
      (node (ref "J1") (pin "P7") (pinfunction "DAT0_P7") (pintype "bidirectional"))
      (node (ref "R2") (pin "1") (pinfunction "1_1") (pintype "passive"))
      (node (ref "TP6") (pin "TP") (pinfunction "TP_TP") (pintype "input"))
      (node (ref "U1") (pin "27") (pinfunction "IO2_27") (pintype "bidirectional"))
      (node (ref "U3") (pin "2") (pinfunction "DO(IO1)_2") (pintype "bidirectional"))
    )
    (net (code "20") (name "MOSI") (class "Default")
      (node (ref "D2") (pin "2") (pinfunction "2_2") (pintype "passive"))
      (node (ref "J1") (pin "P3") (pinfunction "CMD_P3") (pintype "bidirectional"))
      (node (ref "J3") (pin "14") (pinfunction "14_14") (pintype "bidirectional"))
      (node (ref "R3") (pin "1") (pinfunction "1_1") (pintype "passive"))
      (node (ref "TP7") (pin "TP") (pinfunction "TP_TP") (pintype "input"))
      (node (ref "U1") (pin "7") (pinfunction "IO7_7") (pintype "bidirectional"))
      (node (ref "U3") (pin "5") (pinfunction "DI(IO0)_5") (pintype "bidirectional"))
    )
    (net (code "21") (name "Net-(CHG_LED-PadC)") (class "Default")
      (node (ref "CHG_LED") (pin "C") (pinfunction "C_C") (pintype "passive"))
      (node (ref "R1_BAT") (pin "2") (pinfunction "2_2") (pintype "passive"))
    )
    (net (code "22") (name "Net-(D7-CATHODE)") (class "Default")
      (node (ref "D7") (pin "1") (pinfunction "CATHODE_1") (pintype "bidirectional"))
      (node (ref "R_CAPACITOR") (pin "2") (pinfunction "2_2") (pintype "passive"))
    )
    (net (code "23") (name "Net-(D10-A)") (class "Default")
      (node (ref "C7") (pin "1") (pinfunction "1_1") (pintype "passive"))
      (node (ref "D10") (pin "2") (pinfunction "A_2") (pintype "bidirectional"))
      (node (ref "D9") (pin "1") (pinfunction "K_1") (pintype "bidirectional"))
    )
    (net (code "24") (name "Net-(DMG2305UX-7-S)") (class "Default")
      (node (ref "C1_BAT1") (pin "1") (pinfunction "1_1") (pintype "passive"))
      (node (ref "DMG2305UX-7") (pin "2") (pinfunction "S_2") (pintype "bidirectional"))
      (node (ref "IC1") (pin "1") (pinfunction "VIN_1") (pintype "bidirectional"))
      (node (ref "IC1") (pin "3") (pinfunction "CE_3") (pintype "bidirectional"))
      (node (ref "SD0805S020S1R0") (pin "1") (pinfunction "CATHODE_1") (pintype "bidirectional"))
    )
    (net (code "25") (name "Net-(EPD_C1-Pad1)") (class "Default")
      (node (ref "EPD_C1") (pin "1") (pinfunction "1_1") (pintype "passive"))
      (node (ref "J3") (pin "4") (pinfunction "4_4") (pintype "bidirectional"))
    )
    (net (code "26") (name "Net-(EPD_C2-Pad1)") (class "Default")
      (node (ref "EPD_C2") (pin "1") (pinfunction "1_1") (pintype "passive"))
      (node (ref "J3") (pin "5") (pinfunction "5_5") (pintype "bidirectional"))
    )
    (net (code "27") (name "Net-(EPD_C6-Pad1)") (class "Default")
      (node (ref "EPD_C6") (pin "1") (pinfunction "1_1") (pintype "passive"))
      (node (ref "J3") (pin "18") (pinfunction "18_18") (pintype "bidirectional"))
    )
    (net (code "28") (name "Net-(EPD_C7-Pad1)") (class "Default")
      (node (ref "EPD_C7") (pin "1") (pinfunction "1_1") (pintype "passive"))
      (node (ref "J3") (pin "19") (pinfunction "19_19") (pintype "bidirectional"))
    )
    (net (code "29") (name "Net-(EPD_C8-Pad1)") (class "Default")
      (node (ref "EPD_C8") (pin "1") (pinfunction "1_1") (pintype "passive"))
      (node (ref "J3") (pin "20") (pinfunction "20_20") (pintype "bidirectional"))
    )
    (net (code "30") (name "Net-(EPD_C10-Pad1)") (class "Default")
      (node (ref "EPD_C10") (pin "1") (pinfunction "1_1") (pintype "passive"))
      (node (ref "J3") (pin "22") (pinfunction "22_22") (pintype "bidirectional"))
    )
    (net (code "31") (name "Net-(EPD_C12-Pad1)") (class "Default")
      (node (ref "EPD_C12") (pin "1") (pinfunction "1_1") (pintype "passive"))
      (node (ref "J3") (pin "24") (pinfunction "24_24") (pintype "bidirectional"))
    )
    (net (code "32") (name "Net-(IC2-CT)") (class "Default")
      (node (ref "C_DELAY") (pin "1") (pinfunction "1_1") (pintype "passive"))
      (node (ref "IC2") (pin "5") (pinfunction "CT_5") (pintype "bidirectional"))
    )
    (net (code "33") (name "Net-(J4-PadA5)") (class "Default")
      (node (ref "J4") (pin "A5") (pinfunction "A5_A5") (pintype "bidirectional"))
      (node (ref "R2-USB1") (pin "2") (pinfunction "2_2") (pintype "passive"))
    )
    (net (code "34") (name "Net-(J4-PadB5)") (class "Default")
      (node (ref "J4") (pin "B5") (pinfunction "B5_B5") (pintype "bidirectional"))
      (node (ref "R2-USB") (pin "1") (pinfunction "1_1") (pintype "passive"))
    )
    (net (code "35") (name "Net-(MCP73831-PROG)") (class "Default")
      (node (ref "MCP73831") (pin "5") (pinfunction "PROG_5") (pintype "input"))
      (node (ref "R2_BAT") (pin "2") (pinfunction "2_2") (pintype "passive"))
    )
    (net (code "36") (name "Net-(MCP73831-STAT)") (class "Default")
      (node (ref "MCP73831") (pin "1") (pinfunction "STAT_1") (pintype "output"))
      (node (ref "R1_BAT") (pin "1") (pinfunction "1_1") (pintype "passive"))
    )
    (net (code "37") (name "PREVGH") (class "Default")
      (node (ref "D8") (pin "1") (pinfunction "K_1") (pintype "bidirectional"))
      (node (ref "EPD_C9") (pin "1") (pinfunction "1_1") (pintype "passive"))
      (node (ref "J3") (pin "21") (pinfunction "21_21") (pintype "bidirectional"))
    )
    (net (code "38") (name "PREVGL") (class "Default")
      (node (ref "D9") (pin "2") (pinfunction "A_2") (pintype "bidirectional"))
      (node (ref "EPD_C11") (pin "1") (pinfunction "1_1") (pintype "passive"))
      (node (ref "J3") (pin "23") (pinfunction "23_23") (pintype "bidirectional"))
    )
    (net (code "39") (name "RESE") (class "Default")
      (node (ref "J3") (pin "3") (pinfunction "3_3") (pintype "bidirectional"))
      (node (ref "Q2") (pin "2") (pinfunction "S_2") (pintype "bidirectional"))
      (node (ref "R10") (pin "1") (pinfunction "1_1") (pintype "passive"))
    )
    (net (code "40") (name "RESE'") (class "Default")
      (node (ref "R10") (pin "2") (pinfunction "2_2") (pintype "passive"))
      (node (ref "R8") (pin "2") (pinfunction "2_2") (pintype "passive"))
      (node (ref "SJ1") (pin "2") (pinfunction "2_2") (pintype "passive"))
    )
    (net (code "41") (name "RESET") (class "Default")
      (node (ref "C2") (pin "1") (pinfunction "1_1") (pintype "passive"))
      (node (ref "IC2") (pin "1") (pinfunction "VOUT_1") (pintype "bidirectional"))
      (node (ref "RESET_BUTTON") (pin "3") (pinfunction "3_3") (pintype "passive"))
      (node (ref "RESET_BUTTON") (pin "4") (pinfunction "4_4") (pintype "passive"))
      (node (ref "R_RESET") (pin "2") (pinfunction "2_2") (pintype "passive"))
      (node (ref "U1") (pin "3") (pinfunction "EN_3") (pintype "input"))
    )
    (net (code "42") (name "RTC_RST") (class "Default")
      (node (ref "U1") (pin "16") (pinfunction "IO18_16") (pintype "bidirectional"))
      (node (ref "U4") (pin "4") (pinfunction "~{RST}_4") (pintype "input"))
    )
    (net (code "43") (name "RX") (class "Default")
      (node (ref "TP2") (pin "TP") (pinfunction "TP_TP") (pintype "input"))
      (node (ref "U1") (pin "24") (pinfunction "RXD0/GPIO17_24") (pintype "bidirectional"))
    )
    (net (code "44") (name "SCK") (class "Default")
      (node (ref "D3") (pin "2") (pinfunction "2_2") (pintype "passive"))
      (node (ref "J1") (pin "P5") (pinfunction "CLK_P5") (pintype "bidirectional"))
      (node (ref "J3") (pin "13") (pinfunction "13_13") (pintype "bidirectional"))
      (node (ref "R4") (pin "1") (pinfunction "1_1") (pintype "passive"))
      (node (ref "TP8") (pin "TP") (pinfunction "TP_TP") (pintype "input"))
      (node (ref "U1") (pin "6") (pinfunction "IO6_6") (pintype "bidirectional"))
      (node (ref "U3") (pin "6") (pinfunction "CLK_6") (pintype "input"))
    )
    (net (code "45") (name "SCL") (class "Default")
      (node (ref "J2") (pin "4") (pinfunction "4_4") (pintype "passive"))
      (node (ref "R2-PINH") (pin "1") (pinfunction "1_1") (pintype "passive"))
      (node (ref "SENSOR2") (pin "4") (pinfunction "SCK_4") (pintype "input"))
      (node (ref "U1") (pin "20") (pinfunction "IO22_20") (pintype "bidirectional"))
      (node (ref "U2") (pin "7") (pinfunction "SCL_7") (pintype "input"))
      (node (ref "U4") (pin "16") (pinfunction "SCL_16") (pintype "input"))
    )
    (net (code "46") (name "SDA") (class "Default")
      (node (ref "J2") (pin "3") (pinfunction "3_3") (pintype "passive"))
      (node (ref "R1_PINH") (pin "1") (pinfunction "1_1") (pintype "passive"))
      (node (ref "SENSOR2") (pin "3") (pinfunction "SDI_3") (pintype "bidirectional"))
      (node (ref "U1") (pin "19") (pinfunction "IO21_19") (pintype "bidirectional"))
      (node (ref "U2") (pin "8") (pinfunction "SDA_8") (pintype "bidirectional"))
      (node (ref "U4") (pin "15") (pinfunction "SDA_15") (pintype "bidirectional"))
    )
    (net (code "47") (name "SRC") (class "Default")
      (node (ref "C7") (pin "2") (pinfunction "2_2") (pintype "passive"))
      (node (ref "D8") (pin "2") (pinfunction "A_2") (pintype "bidirectional"))
      (node (ref "L1") (pin "1") (pinfunction "1_1") (pintype "passive"))
      (node (ref "Q2") (pin "3") (pinfunction "D_3") (pintype "bidirectional"))
    )
    (net (code "48") (name "SS_SD") (class "Default")
      (node (ref "D6") (pin "2") (pinfunction "2_2") (pintype "passive"))
      (node (ref "J1") (pin "P2") (pinfunction "CD/DAT3_P2") (pintype "bidirectional"))
      (node (ref "R7") (pin "1") (pinfunction "1_1") (pintype "passive"))
      (node (ref "U1") (pin "4") (pinfunction "IO4_4") (pintype "bidirectional"))
    )
    (net (code "49") (name "TX") (class "Default")
      (node (ref "TP1") (pin "TP") (pinfunction "TP_TP") (pintype "input"))
      (node (ref "U1") (pin "25") (pinfunction "TXD0/GPIO16_25") (pintype "bidirectional"))
    )
    (net (code "50") (name "USB_D+") (class "Default")
      (node (ref "D11") (pin "1") (pinfunction "I/O1_1_1") (pintype "bidirectional"))
      (node (ref "U1") (pin "14") (pinfunction "IO13_14") (pintype "bidirectional"))
    )
    (net (code "51") (name "USB_D-") (class "Default")
      (node (ref "D11") (pin "3") (pinfunction "I/O2_1_3") (pintype "bidirectional"))
      (node (ref "U1") (pin "13") (pinfunction "IO12_13") (pintype "bidirectional"))
    )
    (net (code "52") (name "VBAT") (class "Default")
      (node (ref "C2_BAT") (pin "1") (pinfunction "1_1") (pintype "passive"))
      (node (ref "DMG2305UX-7") (pin "3") (pinfunction "D_3") (pintype "bidirectional"))
      (node (ref "MCP73831") (pin "3") (pinfunction "VBAT_3") (pintype "power_in"))
      (node (ref "TP3") (pin "TP") (pinfunction "TP_TP") (pintype "input"))
      (node (ref "U2") (pin "2") (pinfunction "CELL_2") (pintype "power_in"))
      (node (ref "U2") (pin "3") (pinfunction "VDD_3") (pintype "power_in"))
    )
    (net (code "53") (name "VBUS") (class "Default")
      (node (ref "C1_BAT") (pin "1") (pinfunction "1_1") (pintype "passive"))
      (node (ref "C4_USB") (pin "1") (pinfunction "1_1") (pintype "passive"))
      (node (ref "C5_USB") (pin "1") (pinfunction "1_1") (pintype "passive"))
      (node (ref "CHG_LED") (pin "A") (pinfunction "A_A") (pintype "passive"))
      (node (ref "D11") (pin "5") (pinfunction "VBUS_5") (pintype "bidirectional"))
      (node (ref "DMG2305UX-7") (pin "1") (pinfunction "G_1") (pintype "bidirectional"))
      (node (ref "MCP73831") (pin "4") (pinfunction "VIN_4") (pintype "power_in"))
      (node (ref "PFMF.050.1") (pin "2") (pinfunction "2_2") (pintype "passive"))
      (node (ref "R1_PWRUSB") (pin "2") (pinfunction "2_2") (pintype "passive"))
      (node (ref "SD0805S020S1R0") (pin "2") (pinfunction "ANODE_2") (pintype "bidirectional"))
      (node (ref "TP14") (pin "TP") (pinfunction "TP_TP") (pintype "input"))
    )
    (net (code "54") (name "VRTC") (class "Default")
      (node (ref "C10_SUPERCAP") (pin "2") (pinfunction "2_2") (pintype "passive"))
      (node (ref "C6") (pin "1") (pinfunction "1_1") (pintype "passive"))
      (node (ref "R_CAPACITOR") (pin "1") (pinfunction "1_1") (pintype "passive"))
      (node (ref "U4") (pin "14") (pinfunction "VBAT_14") (pintype "power_in"))
    )
    (net (code "55") (name "VUSB") (class "Default")
      (node (ref "J4") (pin "A4") (pinfunction "A4_A4") (pintype "bidirectional"))
      (node (ref "J4") (pin "A9") (pinfunction "A9_A9") (pintype "bidirectional"))
      (node (ref "J4") (pin "B4") (pinfunction "B4_B4") (pintype "bidirectional"))
      (node (ref "J4") (pin "B9") (pinfunction "B9_B9") (pintype "bidirectional"))
      (node (ref "PFMF.050.1") (pin "1") (pinfunction "1_1") (pintype "passive"))
    )
    (net (code "56") (name "unconnected-(IC1-NC-Pad4)") (class "Default")
      (node (ref "IC1") (pin "4") (pinfunction "NC_4") (pintype "no_connect"))
    )
    (net (code "57") (name "unconnected-(IC2-NC-Pad4)") (class "Default")
      (node (ref "IC2") (pin "4") (pinfunction "NC_4") (pintype "no_connect"))
    )
    (net (code "58") (name "unconnected-(J1-DAT1-PadP8)") (class "Default")
      (node (ref "J1") (pin "P8") (pinfunction "DAT1_P8") (pintype "bidirectional"))
    )
    (net (code "59") (name "unconnected-(J1-DAT2-PadP1)") (class "Default")
      (node (ref "J1") (pin "P1") (pinfunction "DAT2_P1") (pintype "bidirectional"))
    )
    (net (code "60") (name "unconnected-(J1-DETECTION_1-PadS1)") (class "Default")
      (node (ref "J1") (pin "S1") (pinfunction "DETECTION_1_S1") (pintype "bidirectional"))
    )
    (net (code "61") (name "unconnected-(J1-DETECTION_2-PadS2)") (class "Default")
      (node (ref "J1") (pin "S2") (pinfunction "DETECTION_2_S2") (pintype "bidirectional"))
    )
    (net (code "62") (name "unconnected-(J3-Pad1)") (class "Default")
      (node (ref "J3") (pin "1") (pinfunction "1_1") (pintype "bidirectional"))
    )
    (net (code "63") (name "unconnected-(J3-Pad6)") (class "Default")
      (node (ref "J3") (pin "6") (pinfunction "6_6") (pintype "bidirectional"))
    )
    (net (code "64") (name "unconnected-(J3-Pad7)") (class "Default")
      (node (ref "J3") (pin "7") (pinfunction "7_7") (pintype "bidirectional"))
    )
    (net (code "65") (name "unconnected-(J4-PadA8)") (class "Default")
      (node (ref "J4") (pin "A8") (pinfunction "A8_A8") (pintype "bidirectional"))
    )
    (net (code "66") (name "unconnected-(J4-PadB8)") (class "Default")
      (node (ref "J4") (pin "B8") (pinfunction "B8_B8") (pintype "bidirectional"))
    )
    (net (code "67") (name "unconnected-(U1-NC-Pad22)") (class "Default")
      (node (ref "U1") (pin "22") (pinfunction "NC_22") (pintype "no_connect"))
    )
    (net (code "68") (name "unconnected-(U2-~{ALERT}-Pad5)") (class "Default")
      (node (ref "U2") (pin "5") (pinfunction "~{ALERT}_5") (pintype "output"))
    )
  )
)
